# SW6121_A_A_B_LED.net
KiCad netlist of a schematic drawn in Altium Designer
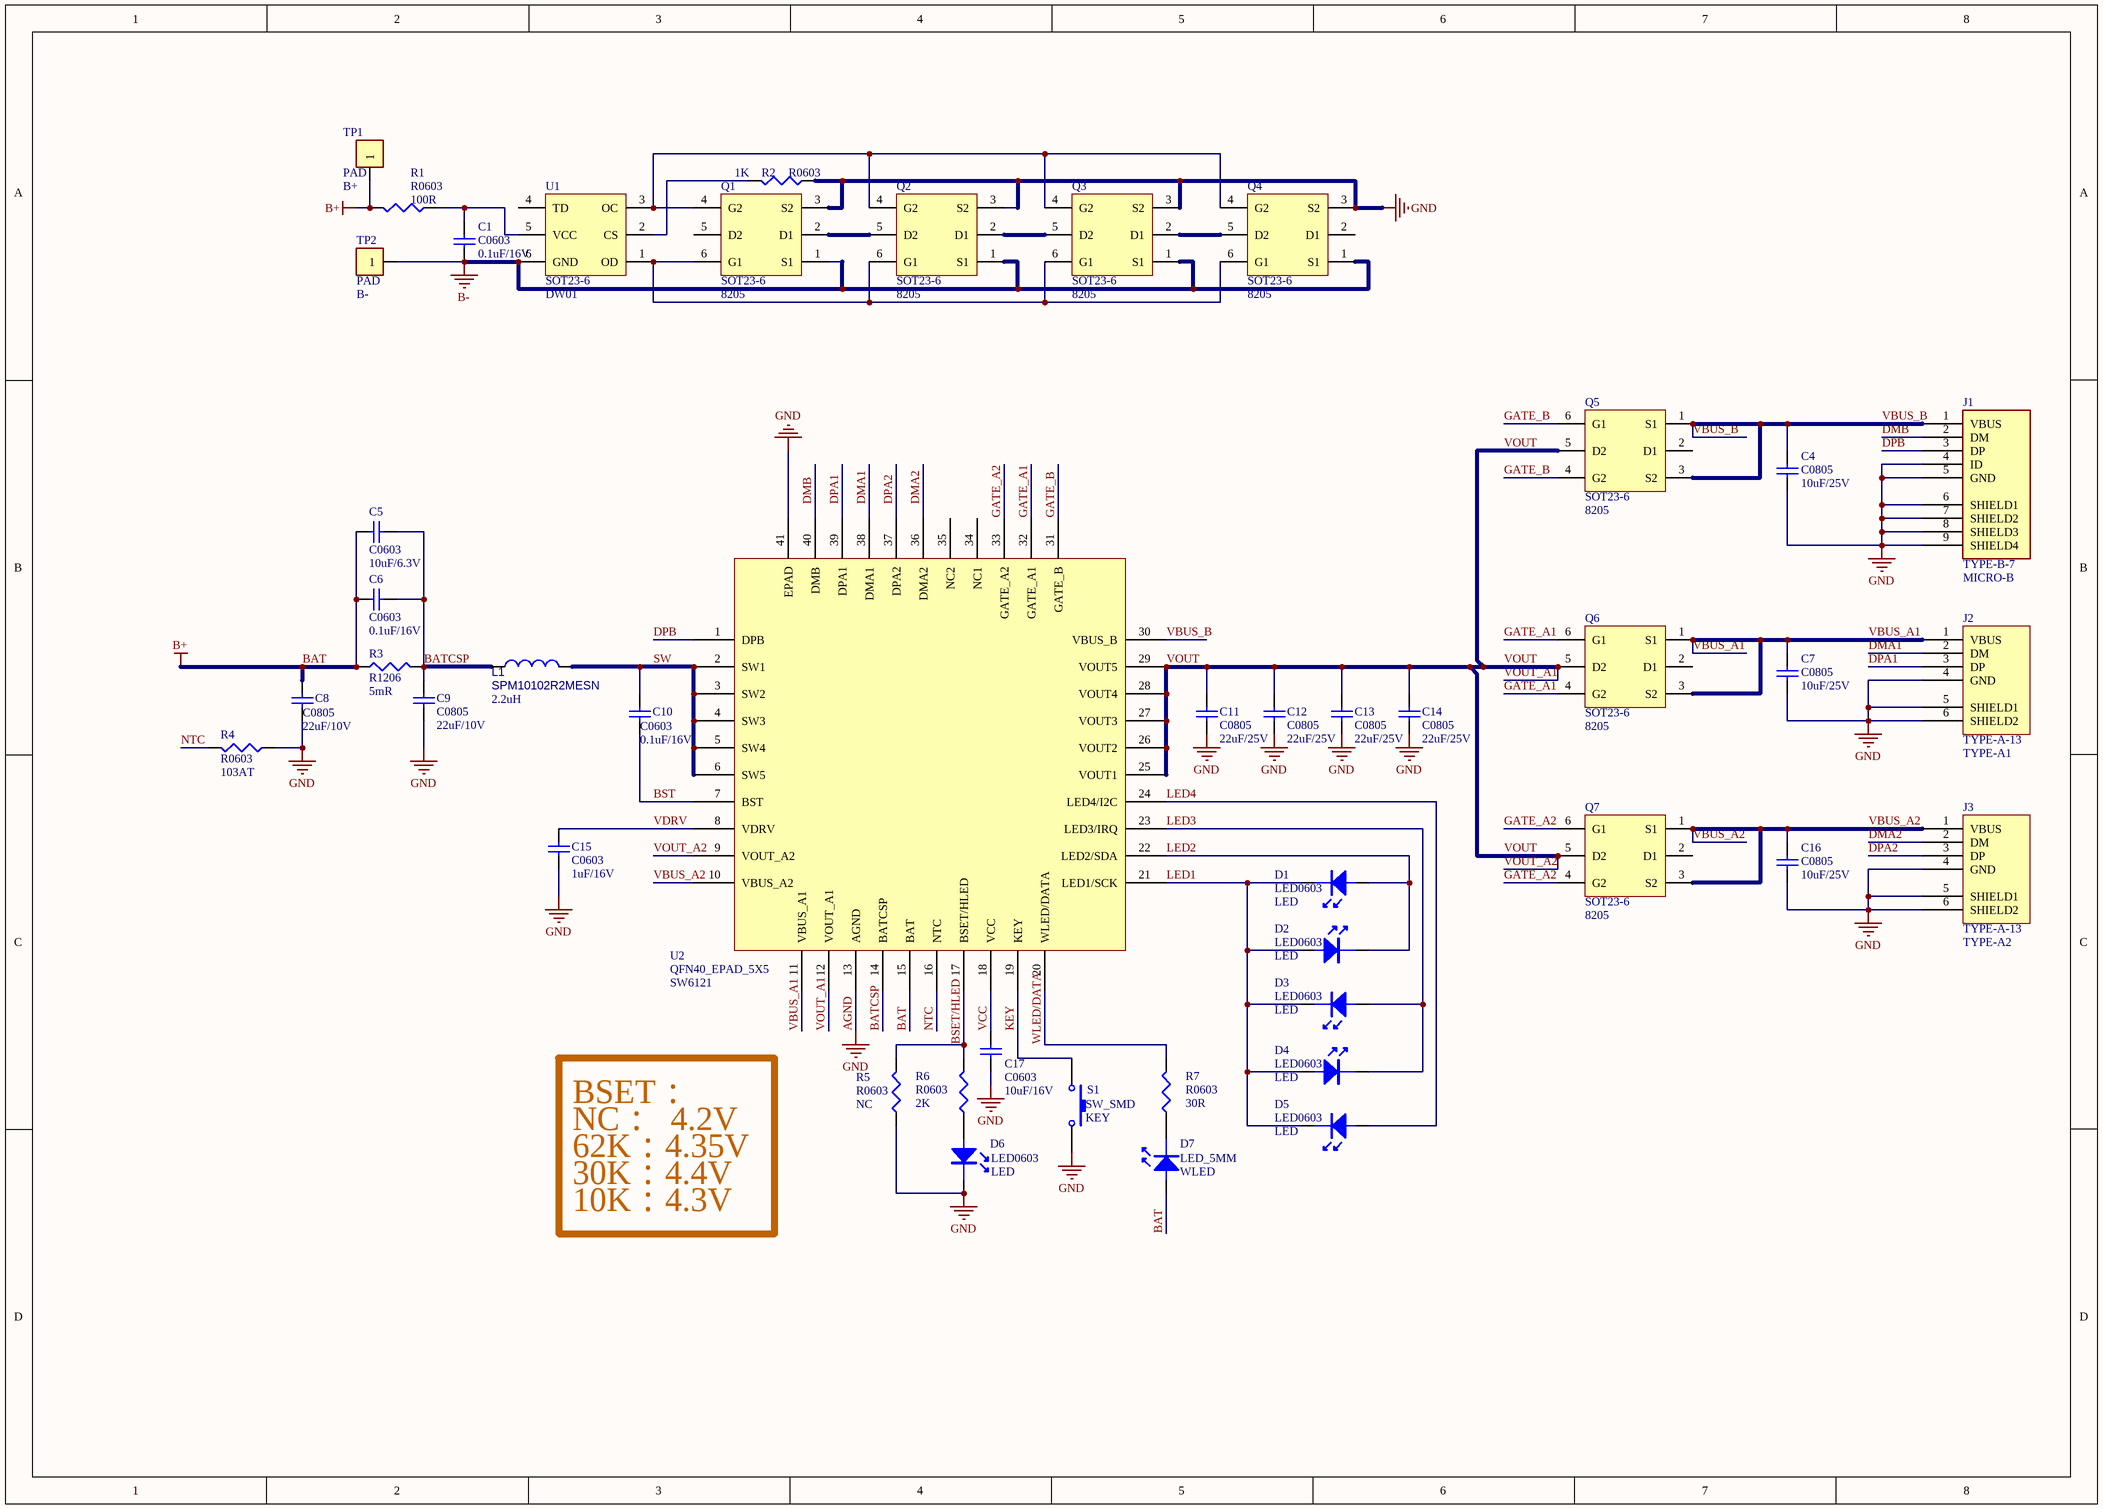
[diagram p0: SW6121+A+A+B+LED.SchDoc]

(export (version "E")
  (design (tool "Eeschema 10.0.6"))
  (components
    (comp (ref "C1")
      (value "C0603")
      (footprint "C0603")
      (description "Capacitor")
      (fields (field (name "ALTIUM_VALUE") "0.1uF/16V") (field (name "PUBLISHER") "Altium Limited"))
      (libsource (lib "*") (part "Cap"))
    )
    (comp (ref "C4")
      (value "C0805")
      (footprint "C0805")
      (description "Capacitor")
      (fields (field (name "ALTIUM_VALUE") "10uF/25V") (field (name "PUBLISHER") "Altium Limited"))
      (libsource (lib "*") (part "CAP0603"))
    )
    (comp (ref "C5")
      (value "C0603")
      (footprint "C0603")
      (description "Capacitor")
      (fields (field (name "ALTIUM_VALUE") "10uF/6.3V") (field (name "PUBLISHER") "Altium Limited"))
      (libsource (lib "*") (part "CAP0603"))
    )
    (comp (ref "C6")
      (value "C0603")
      (footprint "C0603")
      (description "Capacitor")
      (fields (field (name "ALTIUM_VALUE") "0.1uF/16V") (field (name "PUBLISHER") "Altium Limited"))
      (libsource (lib "*") (part "CAP0603"))
    )
    (comp (ref "C7")
      (value "C0805")
      (footprint "C0805")
      (description "Capacitor")
      (fields (field (name "ALTIUM_VALUE") "10uF/25V") (field (name "PUBLISHER") "Altium Limited"))
      (libsource (lib "*") (part "CAP0603"))
    )
    (comp (ref "C8")
      (value "C0805")
      (footprint "C0805")
      (description "Capacitor")
      (fields (field (name "ALTIUM_VALUE") "22uF/10V") (field (name "PUBLISHER") "Altium Limited"))
      (libsource (lib "*") (part "CAP0805"))
    )
    (comp (ref "C9")
      (value "C0805")
      (footprint "C0805")
      (description "Capacitor")
      (fields (field (name "ALTIUM_VALUE") "22uF/10V") (field (name "PUBLISHER") "Altium Limited"))
      (libsource (lib "*") (part "CAP0805"))
    )
    (comp (ref "C10")
      (value "C0603")
      (footprint "C0603")
      (description "Capacitor")
      (fields (field (name "ALTIUM_VALUE") "0.1uF/16V") (field (name "PUBLISHER") "Altium Limited"))
      (libsource (lib "*") (part "CAP0603"))
    )
    (comp (ref "C11")
      (value "C0805")
      (footprint "C0805")
      (description "Capacitor")
      (fields (field (name "ALTIUM_VALUE") "22uF/25V") (field (name "PUBLISHER") "Altium Limited"))
      (libsource (lib "*") (part "CAP0805"))
    )
    (comp (ref "C12")
      (value "C0805")
      (footprint "C0805")
      (description "Capacitor")
      (fields (field (name "ALTIUM_VALUE") "22uF/25V") (field (name "PUBLISHER") "Altium Limited"))
      (libsource (lib "*") (part "CAP0805"))
    )
    (comp (ref "C13")
      (value "C0805")
      (footprint "C0805")
      (description "Capacitor")
      (fields (field (name "ALTIUM_VALUE") "22uF/25V") (field (name "PUBLISHER") "Altium Limited"))
      (libsource (lib "*") (part "CAP0805"))
    )
    (comp (ref "C14")
      (value "C0805")
      (footprint "C0805")
      (description "Capacitor")
      (fields (field (name "ALTIUM_VALUE") "22uF/25V") (field (name "PUBLISHER") "Altium Limited"))
      (libsource (lib "*") (part "CAP0805"))
    )
    (comp (ref "C15")
      (value "C0603")
      (footprint "C0603")
      (description "Capacitor")
      (fields (field (name "ALTIUM_VALUE") "1uF/16V") (field (name "PUBLISHER") "Altium Limited"))
      (libsource (lib "*") (part "CAP0603"))
    )
    (comp (ref "C16")
      (value "C0805")
      (footprint "C0805")
      (description "Capacitor")
      (fields (field (name "ALTIUM_VALUE") "10uF/25V") (field (name "PUBLISHER") "Altium Limited"))
      (libsource (lib "*") (part "CAP0603"))
    )
    (comp (ref "C17")
      (value "C0603")
      (footprint "C0603")
      (description "Capacitor")
      (fields (field (name "ALTIUM_VALUE") "10uF/16V") (field (name "PUBLISHER") "Altium Limited"))
      (libsource (lib "*") (part "CAP0603"))
    )
    (comp (ref "D1") (value "LED") (footprint "LED0603") (libsource (lib "*") (part "LED")))
    (comp (ref "D2") (value "LED") (footprint "LED0603") (libsource (lib "*") (part "LED")))
    (comp (ref "D3") (value "LED") (footprint "LED0603") (libsource (lib "*") (part "LED")))
    (comp (ref "D4") (value "LED") (footprint "LED0603") (libsource (lib "*") (part "LED")))
    (comp (ref "D5") (value "LED") (footprint "LED0603") (libsource (lib "*") (part "LED")))
    (comp (ref "D6") (value "LED") (footprint "LED0603") (libsource (lib "*") (part "LED")))
    (comp (ref "D7")
      (value "WLED")
      (footprint "LED_5MM")
      (fields (field (name "FOOTPRINF") "LED_5MM") (field (name "Comment") "LED_5MM"))
      (libsource (lib "*") (part "LED"))
    )
    (comp (ref "J1")
      (value "MICRO-B")
      (footprint "TYPE-B-7")
      (fields (field (name "FOOTPRINTF") "TYPE-B-7") (field (name "Comment") "USB_MICRO_B"))
      (libsource (lib "*") (part "USB_MICRO_B"))
    )
    (comp (ref "J2")
      (value "TYPE-A1")
      (footprint "TYPE-A-13")
      (fields (field (name "FOOTPRINF") "TYPE-A-13") (field (name "Comment") "TYPE-A-1"))
      (libsource (lib "*") (part "TYPE-A-1"))
    )
    (comp (ref "J3")
      (value "TYPE-A2")
      (footprint "TYPE-A-13")
      (fields (field (name "FOOTPRINF") "TYPE-A-13") (field (name "Comment") "TYPE-A-1"))
      (libsource (lib "*") (part "TYPE-A-1"))
    )
    (comp (ref "L1")
      (value "SPM10102R2MESN")
      (footprint "INDUCTOR_SPM1010")
      (fields (field (name "ALTIUM_VALUE") "2.2uH"))
      (libsource (lib "*") (part "INDUCTOR"))
    )
    (comp (ref "Q1")
      (value "8205")
      (footprint "SOT23-6")
      (fields (field (name "FOOTPRINF") "SOT23-6"))
      (libsource (lib "") (part "8205B_1"))
    )
    (comp (ref "Q2")
      (value "8205")
      (footprint "SOT23-6")
      (fields (field (name "FOOTPRINF") "SOT23-6"))
      (libsource (lib "") (part "8205B_1"))
    )
    (comp (ref "Q3")
      (value "8205")
      (footprint "SOT23-6")
      (fields (field (name "FOOTPRINF") "SOT23-6"))
      (libsource (lib "") (part "8205B_1"))
    )
    (comp (ref "Q4")
      (value "8205")
      (footprint "SOT23-6")
      (fields (field (name "FOOTPRINF") "SOT23-6"))
      (libsource (lib "") (part "8205B_1"))
    )
    (comp (ref "Q5")
      (value "8205")
      (footprint "SOT23-6")
      (fields (field (name "FOOTPRINF") "SOT23-6"))
      (libsource (lib "*") (part "8205B"))
    )
    (comp (ref "Q6")
      (value "8205")
      (footprint "SOT23-6")
      (fields (field (name "FOOTPRINF") "SOT23-6"))
      (libsource (lib "*") (part "8205B"))
    )
    (comp (ref "Q7")
      (value "8205")
      (footprint "SOT23-6")
      (fields (field (name "FOOTPRINF") "SOT23-6"))
      (libsource (lib "*") (part "8205B"))
    )
    (comp (ref "R1")
      (value "R0603")
      (footprint "R0603")
      (description "Resistor")
      (fields (field (name "ALTIUM_VALUE") "100R") (field (name "PUBLISHER") "Altium Limited"))
      (libsource (lib "*") (part "Res3"))
    )
    (comp (ref "R2")
      (value "R0603")
      (footprint "R0603")
      (description "Resistor")
      (fields (field (name "ALTIUM_VALUE") "1K") (field (name "PUBLISHER") "Altium Limited"))
      (libsource (lib "*") (part "Res3"))
    )
    (comp (ref "R3")
      (value "R1206")
      (footprint "R1206")
      (description "Resistor")
      (fields (field (name "ALTIUM_VALUE") "5mR") (field (name "PUBLISHER") "Altium Limited"))
      (libsource (lib "*") (part "RES"))
    )
    (comp (ref "R4")
      (value "R0603")
      (footprint "R0603")
      (description "Resistor")
      (fields (field (name "ALTIUM_VALUE") "103AT") (field (name "PUBLISHER") "Altium Limited"))
      (libsource (lib "*") (part "RES"))
    )
    (comp (ref "R5")
      (value "R0603")
      (footprint "R0603")
      (description "Resistor")
      (fields (field (name "ALTIUM_VALUE") "NC") (field (name "PUBLISHER") "Altium Limited"))
      (libsource (lib "*") (part "RES"))
    )
    (comp (ref "R6")
      (value "R0603")
      (footprint "R0603")
      (description "Resistor")
      (fields (field (name "ALTIUM_VALUE") "2K") (field (name "PUBLISHER") "Altium Limited"))
      (libsource (lib "*") (part "RES"))
    )
    (comp (ref "R7")
      (value "R0603")
      (footprint "R0603")
      (description "Resistor")
      (fields (field (name "ALTIUM_VALUE") "30R") (field (name "PUBLISHER") "Altium Limited"))
      (libsource (lib "*") (part "RES"))
    )
    (comp (ref "S1")
      (value "KEY")
      (footprint "SW_SMD")
      (fields (field (name "FOOTPRINF") "SW_SMD"))
      (libsource (lib "*") (part "SW K"))
    )
    (comp (ref "TP1") (value "B+") (footprint "PAD") (libsource (lib "*") (part "Test Point")))
    (comp (ref "TP2") (value "B-") (footprint "PAD") (libsource (lib "") (part "Test Point_1")))
    (comp (ref "U1")
      (value "DW01")
      (footprint "SOT23-6")
      (fields (field (name "FOOTPRINF") "SOT23-6"))
      (libsource (lib "*") (part "DW01"))
    )
    (comp (ref "U2")
      (value "SW6121")
      (footprint "QFN40_EPAD_5X5")
      (libsource (lib "SW6120+A+A+B+LED") (part "SW6106_AFC"))
    )
  )
  (nets
    (net (code "1") (name "/BATCSP") (class "Default")
      (node (ref "C5") (pin "2") (pinfunction "2_2") (pintype "passive"))
      (node (ref "C6") (pin "2") (pinfunction "2_2") (pintype "passive"))
      (node (ref "C9") (pin "2") (pinfunction "2_2") (pintype "passive"))
      (node (ref "L1") (pin "1") (pinfunction "1_1") (pintype "passive"))
      (node (ref "R3") (pin "2") (pinfunction "2_2") (pintype "passive"))
      (node (ref "U2") (pin "14") (pinfunction "BATCSP_14") (pintype "passive"))
    )
    (net (code "2") (name "/BSET{slash}HLED") (class "Default")
      (node (ref "R5") (pin "2") (pinfunction "2_2") (pintype "passive"))
      (node (ref "R6") (pin "2") (pinfunction "2_2") (pintype "passive"))
      (node (ref "U2") (pin "17") (pinfunction "BSET/HLED_17") (pintype "passive"))
    )
    (net (code "3") (name "/BST") (class "Default")
      (node (ref "C10") (pin "1") (pinfunction "1_1") (pintype "passive"))
      (node (ref "U2") (pin "7") (pinfunction "BST_7") (pintype "passive"))
    )
    (net (code "4") (name "/DMA1") (class "Default")
      (node (ref "J2") (pin "2") (pinfunction "DM_2") (pintype "passive"))
      (node (ref "U2") (pin "38") (pinfunction "DMA1_38") (pintype "passive"))
    )
    (net (code "5") (name "/DMA2") (class "Default")
      (node (ref "J3") (pin "2") (pinfunction "DM_2") (pintype "passive"))
      (node (ref "U2") (pin "36") (pinfunction "DMA2_36") (pintype "passive"))
    )
    (net (code "6") (name "/DMB") (class "Default")
      (node (ref "J1") (pin "2") (pinfunction "DM_2") (pintype "passive"))
      (node (ref "U2") (pin "40") (pinfunction "DMB_40") (pintype "passive"))
    )
    (net (code "7") (name "/DPA1") (class "Default")
      (node (ref "J2") (pin "3") (pinfunction "DP_3") (pintype "passive"))
      (node (ref "U2") (pin "39") (pinfunction "DPA1_39") (pintype "passive"))
    )
    (net (code "8") (name "/DPA2") (class "Default")
      (node (ref "J3") (pin "3") (pinfunction "DP_3") (pintype "passive"))
      (node (ref "U2") (pin "37") (pinfunction "DPA2_37") (pintype "passive"))
    )
    (net (code "9") (name "/DPB") (class "Default")
      (node (ref "J1") (pin "3") (pinfunction "DP_3") (pintype "passive"))
      (node (ref "U2") (pin "1") (pinfunction "DPB_1") (pintype "passive"))
    )
    (net (code "10") (name "/GATE_A1") (class "Default")
      (node (ref "Q6") (pin "4") (pinfunction "G2_4") (pintype "passive"))
      (node (ref "Q6") (pin "6") (pinfunction "G1_6") (pintype "passive"))
      (node (ref "U2") (pin "32") (pinfunction "GATE_A1_32") (pintype "passive"))
    )
    (net (code "11") (name "/GATE_A2") (class "Default")
      (node (ref "Q7") (pin "4") (pinfunction "G2_4") (pintype "passive"))
      (node (ref "Q7") (pin "6") (pinfunction "G1_6") (pintype "passive"))
      (node (ref "U2") (pin "33") (pinfunction "GATE_A2_33") (pintype "passive"))
    )
    (net (code "12") (name "/GATE_B") (class "Default")
      (node (ref "Q5") (pin "4") (pinfunction "G2_4") (pintype "passive"))
      (node (ref "Q5") (pin "6") (pinfunction "G1_6") (pintype "passive"))
      (node (ref "U2") (pin "31") (pinfunction "GATE_B_31") (pintype "passive"))
    )
    (net (code "13") (name "/KEY") (class "Default")
      (node (ref "S1") (pin "1") (pinfunction "1_1") (pintype "passive"))
      (node (ref "U2") (pin "19") (pinfunction "KEY_19") (pintype "passive"))
    )
    (net (code "14") (name "/LED1") (class "Default")
      (node (ref "D1") (pin "2") (pinfunction "K_2") (pintype "passive"))
      (node (ref "D2") (pin "1") (pinfunction "A_1") (pintype "passive"))
      (node (ref "D3") (pin "2") (pinfunction "K_2") (pintype "passive"))
      (node (ref "D4") (pin "1") (pinfunction "A_1") (pintype "passive"))
      (node (ref "D5") (pin "2") (pinfunction "K_2") (pintype "passive"))
      (node (ref "U2") (pin "21") (pinfunction "LED1/SCK_21") (pintype "passive"))
    )
    (net (code "15") (name "/LED2") (class "Default")
      (node (ref "D1") (pin "1") (pinfunction "A_1") (pintype "passive"))
      (node (ref "D2") (pin "2") (pinfunction "K_2") (pintype "passive"))
      (node (ref "U2") (pin "22") (pinfunction "LED2/SDA_22") (pintype "passive"))
    )
    (net (code "16") (name "/LED3") (class "Default")
      (node (ref "D3") (pin "1") (pinfunction "A_1") (pintype "passive"))
      (node (ref "D4") (pin "2") (pinfunction "K_2") (pintype "passive"))
      (node (ref "U2") (pin "23") (pinfunction "LED3/IRQ_23") (pintype "passive"))
    )
    (net (code "17") (name "/LED4") (class "Default")
      (node (ref "D5") (pin "1") (pinfunction "A_1") (pintype "passive"))
      (node (ref "U2") (pin "24") (pinfunction "LED4/I2C_24") (pintype "passive"))
    )
    (net (code "18") (name "/NTC") (class "Default")
      (node (ref "R4") (pin "2") (pinfunction "2_2") (pintype "passive"))
      (node (ref "U2") (pin "16") (pinfunction "NTC_16") (pintype "passive"))
    )
    (net (code "19") (name "/SW") (class "Default")
      (node (ref "C10") (pin "2") (pinfunction "2_2") (pintype "passive"))
      (node (ref "L1") (pin "2") (pinfunction "2_2") (pintype "passive"))
      (node (ref "U2") (pin "2") (pinfunction "SW1_2") (pintype "passive"))
      (node (ref "U2") (pin "3") (pinfunction "SW2_3") (pintype "passive"))
      (node (ref "U2") (pin "4") (pinfunction "SW3_4") (pintype "passive"))
      (node (ref "U2") (pin "5") (pinfunction "SW4_5") (pintype "passive"))
      (node (ref "U2") (pin "6") (pinfunction "SW5_6") (pintype "passive"))
    )
    (net (code "20") (name "/VBUS_A1") (class "Default")
      (node (ref "C7") (pin "2") (pinfunction "2_2") (pintype "passive"))
      (node (ref "J2") (pin "1") (pinfunction "VBUS_1") (pintype "passive"))
      (node (ref "Q6") (pin "1") (pinfunction "S1_1") (pintype "passive"))
      (node (ref "Q6") (pin "3") (pinfunction "S2_3") (pintype "passive"))
      (node (ref "U2") (pin "11") (pinfunction "VBUS_A1_11") (pintype "passive"))
    )
    (net (code "21") (name "/VBUS_A2") (class "Default")
      (node (ref "C16") (pin "2") (pinfunction "2_2") (pintype "passive"))
      (node (ref "J3") (pin "1") (pinfunction "VBUS_1") (pintype "passive"))
      (node (ref "Q7") (pin "1") (pinfunction "S1_1") (pintype "passive"))
      (node (ref "Q7") (pin "3") (pinfunction "S2_3") (pintype "passive"))
      (node (ref "U2") (pin "10") (pinfunction "VBUS_A2_10") (pintype "passive"))
    )
    (net (code "22") (name "/VBUS_B") (class "Default")
      (node (ref "C4") (pin "2") (pinfunction "2_2") (pintype "passive"))
      (node (ref "J1") (pin "1") (pinfunction "VBUS_1") (pintype "passive"))
      (node (ref "Q5") (pin "1") (pinfunction "S1_1") (pintype "passive"))
      (node (ref "Q5") (pin "3") (pinfunction "S2_3") (pintype "passive"))
      (node (ref "U2") (pin "30") (pinfunction "VBUS_B_30") (pintype "passive"))
    )
    (net (code "23") (name "/VCC") (class "Default")
      (node (ref "C17") (pin "2") (pinfunction "2_2") (pintype "passive"))
      (node (ref "U2") (pin "18") (pinfunction "VCC_18") (pintype "passive"))
    )
    (net (code "24") (name "/VDRV") (class "Default")
      (node (ref "C15") (pin "2") (pinfunction "2_2") (pintype "passive"))
      (node (ref "U2") (pin "8") (pinfunction "VDRV_8") (pintype "passive"))
    )
    (net (code "25") (name "/VOUT") (class "Default")
      (node (ref "C11") (pin "2") (pinfunction "2_2") (pintype "passive"))
      (node (ref "C12") (pin "2") (pinfunction "2_2") (pintype "passive"))
      (node (ref "C13") (pin "2") (pinfunction "2_2") (pintype "passive"))
      (node (ref "C14") (pin "2") (pinfunction "2_2") (pintype "passive"))
      (node (ref "Q5") (pin "5") (pinfunction "D2_5") (pintype "passive"))
      (node (ref "Q6") (pin "5") (pinfunction "D2_5") (pintype "passive"))
      (node (ref "Q7") (pin "5") (pinfunction "D2_5") (pintype "passive"))
      (node (ref "U2") (pin "12") (pinfunction "VOUT_A1_12") (pintype "passive"))
      (node (ref "U2") (pin "25") (pinfunction "VOUT1_25") (pintype "passive"))
      (node (ref "U2") (pin "26") (pinfunction "VOUT2_26") (pintype "passive"))
      (node (ref "U2") (pin "27") (pinfunction "VOUT3_27") (pintype "passive"))
      (node (ref "U2") (pin "28") (pinfunction "VOUT4_28") (pintype "passive"))
      (node (ref "U2") (pin "29") (pinfunction "VOUT5_29") (pintype "passive"))
      (node (ref "U2") (pin "9") (pinfunction "VOUT_A2_9") (pintype "passive"))
    )
    (net (code "26") (name "/WLED{slash}DATA") (class "Default")
      (node (ref "R7") (pin "2") (pinfunction "2_2") (pintype "passive"))
      (node (ref "U2") (pin "20") (pinfunction "WLED/DATA_20") (pintype "passive"))
    )
    (net (code "27") (name "B+") (class "Default")
      (node (ref "C5") (pin "1") (pinfunction "1_1") (pintype "passive"))
      (node (ref "C6") (pin "1") (pinfunction "1_1") (pintype "passive"))
      (node (ref "C8") (pin "2") (pinfunction "2_2") (pintype "passive"))
      (node (ref "D7") (pin "1") (pinfunction "A_1") (pintype "passive"))
      (node (ref "R1") (pin "2") (pinfunction "2_2") (pintype "passive"))
      (node (ref "R3") (pin "1") (pinfunction "1_1") (pintype "passive"))
      (node (ref "TP1") (pin "1") (pinfunction "1_1") (pintype "passive"))
      (node (ref "U2") (pin "15") (pinfunction "BAT_15") (pintype "passive"))
    )
    (net (code "28") (name "B-") (class "Default")
      (node (ref "C1") (pin "1") (pinfunction "1_1") (pintype "passive"))
      (node (ref "Q1") (pin "1") (pinfunction "S1_1") (pintype "passive"))
      (node (ref "Q2") (pin "1") (pinfunction "S1_1") (pintype "passive"))
      (node (ref "Q3") (pin "1") (pinfunction "S1_1") (pintype "passive"))
      (node (ref "Q4") (pin "1") (pinfunction "S1_1") (pintype "passive"))
      (node (ref "TP2") (pin "1") (pinfunction "1_1") (pintype "passive"))
      (node (ref "U1") (pin "6") (pinfunction "GND_6") (pintype "passive"))
    )
    (net (code "29") (name "GND") (class "Default")
      (node (ref "C11") (pin "1") (pinfunction "1_1") (pintype "passive"))
      (node (ref "C12") (pin "1") (pinfunction "1_1") (pintype "passive"))
      (node (ref "C13") (pin "1") (pinfunction "1_1") (pintype "passive"))
      (node (ref "C14") (pin "1") (pinfunction "1_1") (pintype "passive"))
      (node (ref "C15") (pin "1") (pinfunction "1_1") (pintype "passive"))
      (node (ref "C16") (pin "1") (pinfunction "1_1") (pintype "passive"))
      (node (ref "C17") (pin "1") (pinfunction "1_1") (pintype "passive"))
      (node (ref "C4") (pin "1") (pinfunction "1_1") (pintype "passive"))
      (node (ref "C7") (pin "1") (pinfunction "1_1") (pintype "passive"))
      (node (ref "C8") (pin "1") (pinfunction "1_1") (pintype "passive"))
      (node (ref "C9") (pin "1") (pinfunction "1_1") (pintype "passive"))
      (node (ref "D6") (pin "2") (pinfunction "K_2") (pintype "passive"))
      (node (ref "J1") (pin "4") (pinfunction "ID_4") (pintype "passive"))
      (node (ref "J1") (pin "5") (pinfunction "GND_5") (pintype "passive"))
      (node (ref "J1") (pin "6") (pinfunction "SHIELD1_6") (pintype "passive"))
      (node (ref "J1") (pin "7") (pinfunction "SHIELD2_7") (pintype "passive"))
      (node (ref "J1") (pin "8") (pinfunction "SHIELD3_8") (pintype "passive"))
      (node (ref "J1") (pin "9") (pinfunction "SHIELD4_9") (pintype "passive"))
      (node (ref "J2") (pin "4") (pinfunction "GND_4") (pintype "passive"))
      (node (ref "J2") (pin "5") (pinfunction "SHIELD1_5") (pintype "passive"))
      (node (ref "J2") (pin "6") (pinfunction "SHIELD2_6") (pintype "passive"))
      (node (ref "J3") (pin "4") (pinfunction "GND_4") (pintype "passive"))
      (node (ref "J3") (pin "5") (pinfunction "SHIELD1_5") (pintype "passive"))
      (node (ref "J3") (pin "6") (pinfunction "SHIELD2_6") (pintype "passive"))
      (node (ref "Q1") (pin "3") (pinfunction "S2_3") (pintype "passive"))
      (node (ref "Q2") (pin "3") (pinfunction "S2_3") (pintype "passive"))
      (node (ref "Q3") (pin "3") (pinfunction "S2_3") (pintype "passive"))
      (node (ref "Q4") (pin "3") (pinfunction "S2_3") (pintype "passive"))
      (node (ref "R2") (pin "1") (pinfunction "1_1") (pintype "passive"))
      (node (ref "R4") (pin "1") (pinfunction "1_1") (pintype "passive"))
      (node (ref "R5") (pin "1") (pinfunction "1_1") (pintype "passive"))
      (node (ref "S1") (pin "2") (pinfunction "2_2") (pintype "passive"))
      (node (ref "U2") (pin "13") (pinfunction "AGND_13") (pintype "passive"))
      (node (ref "U2") (pin "41") (pinfunction "EPAD_41") (pintype "passive"))
    )
    (net (code "30") (name "Net-(D6-A)") (class "Default")
      (node (ref "D6") (pin "1") (pinfunction "A_1") (pintype "passive"))
      (node (ref "R6") (pin "1") (pinfunction "1_1") (pintype "passive"))
    )
    (net (code "31") (name "Net-(D7-K)") (class "Default")
      (node (ref "D7") (pin "2") (pinfunction "K_2") (pintype "passive"))
      (node (ref "R7") (pin "1") (pinfunction "1_1") (pintype "passive"))
    )
    (net (code "32") (name "Net-(Q1-D1)") (class "Default")
      (node (ref "Q1") (pin "2") (pinfunction "D1_2") (pintype "passive"))
      (node (ref "Q2") (pin "5") (pinfunction "D2_5") (pintype "passive"))
    )
    (net (code "33") (name "Net-(Q1-G1)") (class "Default")
      (node (ref "Q1") (pin "6") (pinfunction "G1_6") (pintype "passive"))
      (node (ref "Q2") (pin "6") (pinfunction "G1_6") (pintype "passive"))
      (node (ref "Q3") (pin "6") (pinfunction "G1_6") (pintype "passive"))
      (node (ref "Q4") (pin "6") (pinfunction "G1_6") (pintype "passive"))
      (node (ref "U1") (pin "1") (pinfunction "OD_1") (pintype "passive"))
    )
    (net (code "34") (name "Net-(Q1-G2)") (class "Default")
      (node (ref "Q1") (pin "4") (pinfunction "G2_4") (pintype "passive"))
      (node (ref "Q2") (pin "4") (pinfunction "G2_4") (pintype "passive"))
      (node (ref "Q3") (pin "4") (pinfunction "G2_4") (pintype "passive"))
      (node (ref "Q4") (pin "4") (pinfunction "G2_4") (pintype "passive"))
      (node (ref "U1") (pin "3") (pinfunction "OC_3") (pintype "passive"))
    )
    (net (code "35") (name "Net-(Q2-D1)") (class "Default")
      (node (ref "Q2") (pin "2") (pinfunction "D1_2") (pintype "passive"))
      (node (ref "Q3") (pin "5") (pinfunction "D2_5") (pintype "passive"))
    )
    (net (code "36") (name "Net-(Q3-D1)") (class "Default")
      (node (ref "Q3") (pin "2") (pinfunction "D1_2") (pintype "passive"))
      (node (ref "Q4") (pin "5") (pinfunction "D2_5") (pintype "passive"))
    )
    (net (code "37") (name "Net-(U1-CS)") (class "Default")
      (node (ref "R2") (pin "2") (pinfunction "2_2") (pintype "passive"))
      (node (ref "U1") (pin "2") (pinfunction "CS_2") (pintype "passive"))
    )
    (net (code "38") (name "Net-(U1-VCC)") (class "Default")
      (node (ref "C1") (pin "2") (pinfunction "2_2") (pintype "passive"))
      (node (ref "R1") (pin "1") (pinfunction "1_1") (pintype "passive"))
      (node (ref "U1") (pin "5") (pinfunction "VCC_5") (pintype "passive"))
    )
    (net (code "39") (name "unconnected-(Q1-D2-Pad5)") (class "Default")
      (node (ref "Q1") (pin "5") (pinfunction "D2_5") (pintype "passive"))
    )
    (net (code "40") (name "unconnected-(Q4-D1-Pad2)") (class "Default")
      (node (ref "Q4") (pin "2") (pinfunction "D1_2") (pintype "passive"))
    )
    (net (code "41") (name "unconnected-(Q5-D1-Pad2)") (class "Default")
      (node (ref "Q5") (pin "2") (pinfunction "D1_2") (pintype "passive"))
    )
    (net (code "42") (name "unconnected-(Q6-D1-Pad2)") (class "Default")
      (node (ref "Q6") (pin "2") (pinfunction "D1_2") (pintype "passive"))
    )
    (net (code "43") (name "unconnected-(Q7-D1-Pad2)") (class "Default")
      (node (ref "Q7") (pin "2") (pinfunction "D1_2") (pintype "passive"))
    )
    (net (code "44") (name "unconnected-(U1-TD-Pad4)") (class "Default")
      (node (ref "U1") (pin "4") (pinfunction "TD_4") (pintype "passive"))
    )
    (net (code "45") (name "unconnected-(U2-NC1-Pad34)") (class "Default")
      (node (ref "U2") (pin "34") (pinfunction "NC1_34") (pintype "passive"))
    )
    (net (code "46") (name "unconnected-(U2-NC2-Pad35)") (class "Default")
      (node (ref "U2") (pin "35") (pinfunction "NC2_35") (pintype "passive"))
    )
  )
)
